# Counter.net
KiCad netlist of a schematic drawn in EAGLE
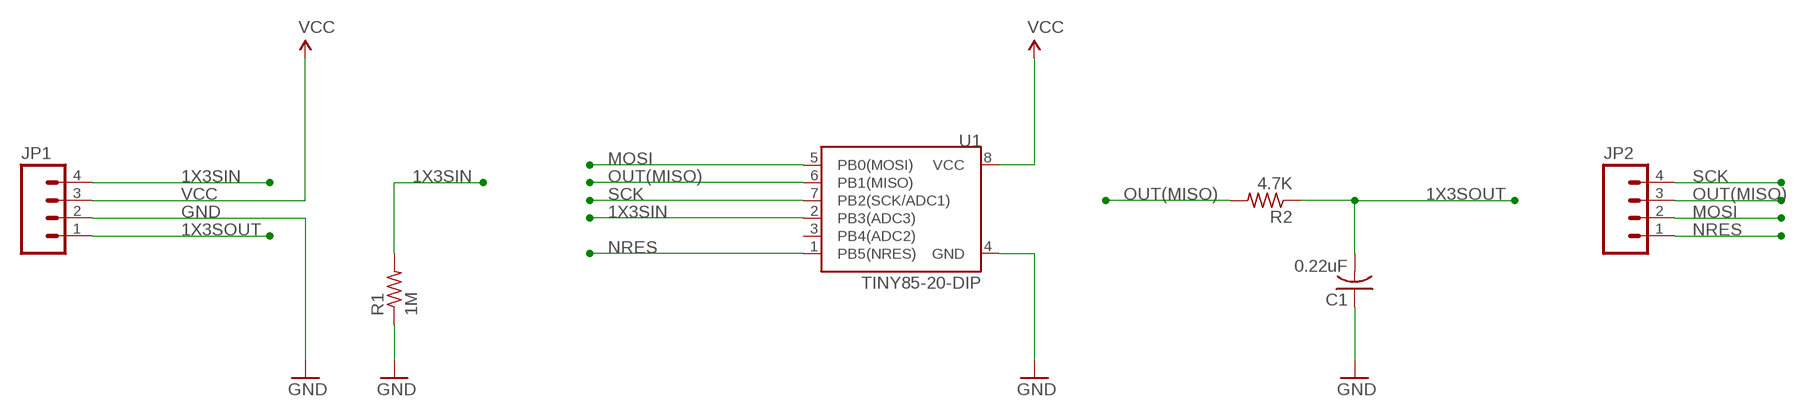
[diagram p0: schematic, sheet 1]

(export (version "E")
  (design (tool "Eeschema 10.0.6"))
  (components
    (comp (ref "C1")
      (value "0.22uF")
      (footprint "eagle-import:C0402")
      (libsource (lib "eagle-import") (part "C-USC0402"))
    )
    (comp (ref "JP1")
      (value "M04PTH")
      (footprint "eagle-import:1X04")
      (libsource (lib "eagle-import") (part "M04PTH"))
    )
    (comp (ref "JP2")
      (value "M04PTH")
      (footprint "eagle-import:1X04")
      (libsource (lib "eagle-import") (part "M04PTH"))
    )
    (comp (ref "R1")
      (value "1M")
      (footprint "eagle-import:R0603")
      (libsource (lib "eagle-import") (part "R-US_R0603"))
    )
    (comp (ref "R2")
      (value "4.7K")
      (footprint "eagle-import:R0603")
      (libsource (lib "eagle-import") (part "R-US_R0603"))
    )
    (comp (ref "U1")
      (value "TINY85-20-DIP")
      (footprint "eagle-import:DIP08")
      (libsource (lib "eagle-import") (part "ATTINY45TINY85-20-DIP"))
    )
  )
  (nets
    (net (code "1") (name "/1X3SIN") (class "Default")
      (node (ref "JP1") (pin "4") (pinfunction "4_4") (pintype "passive"))
      (node (ref "R1") (pin "2") (pinfunction "2_2") (pintype "passive"))
      (node (ref "U1") (pin "2") (pinfunction "PB3(ADC3)_2") (pintype "bidirectional"))
    )
    (net (code "2") (name "/1X3SOUT") (class "Default")
      (node (ref "C1") (pin "2") (pinfunction "2_2") (pintype "passive"))
      (node (ref "JP1") (pin "1") (pinfunction "1_1") (pintype "passive"))
      (node (ref "R2") (pin "1") (pinfunction "1_1") (pintype "passive"))
    )
    (net (code "3") (name "/MOSI") (class "Default")
      (node (ref "JP2") (pin "2") (pinfunction "2_2") (pintype "passive"))
      (node (ref "U1") (pin "5") (pinfunction "PB0(MOSI)_5") (pintype "bidirectional"))
    )
    (net (code "4") (name "/NRES") (class "Default")
      (node (ref "JP2") (pin "1") (pinfunction "1_1") (pintype "passive"))
      (node (ref "U1") (pin "1") (pinfunction "PB5(NRES)_1") (pintype "bidirectional"))
    )
    (net (code "5") (name "/OUT(MISO)") (class "Default")
      (node (ref "JP2") (pin "3") (pinfunction "3_3") (pintype "passive"))
      (node (ref "R2") (pin "2") (pinfunction "2_2") (pintype "passive"))
      (node (ref "U1") (pin "6") (pinfunction "PB1(MISO)_6") (pintype "bidirectional"))
    )
    (net (code "6") (name "/SCK") (class "Default")
      (node (ref "JP2") (pin "4") (pinfunction "4_4") (pintype "passive"))
      (node (ref "U1") (pin "7") (pinfunction "PB2(SCK/ADC1)_7") (pintype "bidirectional"))
    )
    (net (code "7") (name "GND") (class "Default")
      (node (ref "C1") (pin "1") (pinfunction "1_1") (pintype "passive"))
      (node (ref "JP1") (pin "2") (pinfunction "2_2") (pintype "passive"))
      (node (ref "R1") (pin "1") (pinfunction "1_1") (pintype "passive"))
      (node (ref "U1") (pin "4") (pinfunction "GND_4") (pintype "bidirectional"))
    )
    (net (code "8") (name "VCC") (class "Default")
      (node (ref "JP1") (pin "3") (pinfunction "3_3") (pintype "passive"))
      (node (ref "U1") (pin "8") (pinfunction "VCC_8") (pintype "bidirectional"))
    )
    (net (code "9") (name "unconnected-(U1-PB4(ADC2)-Pad3)") (class "Default")
      (node (ref "U1") (pin "3") (pinfunction "PB4(ADC2)_3") (pintype "bidirectional"))
    )
  )
)
